# 1-Schematic_Illuno_Atmega328pu_V1.net
KiCad netlist of a schematic drawn in EasyEDA
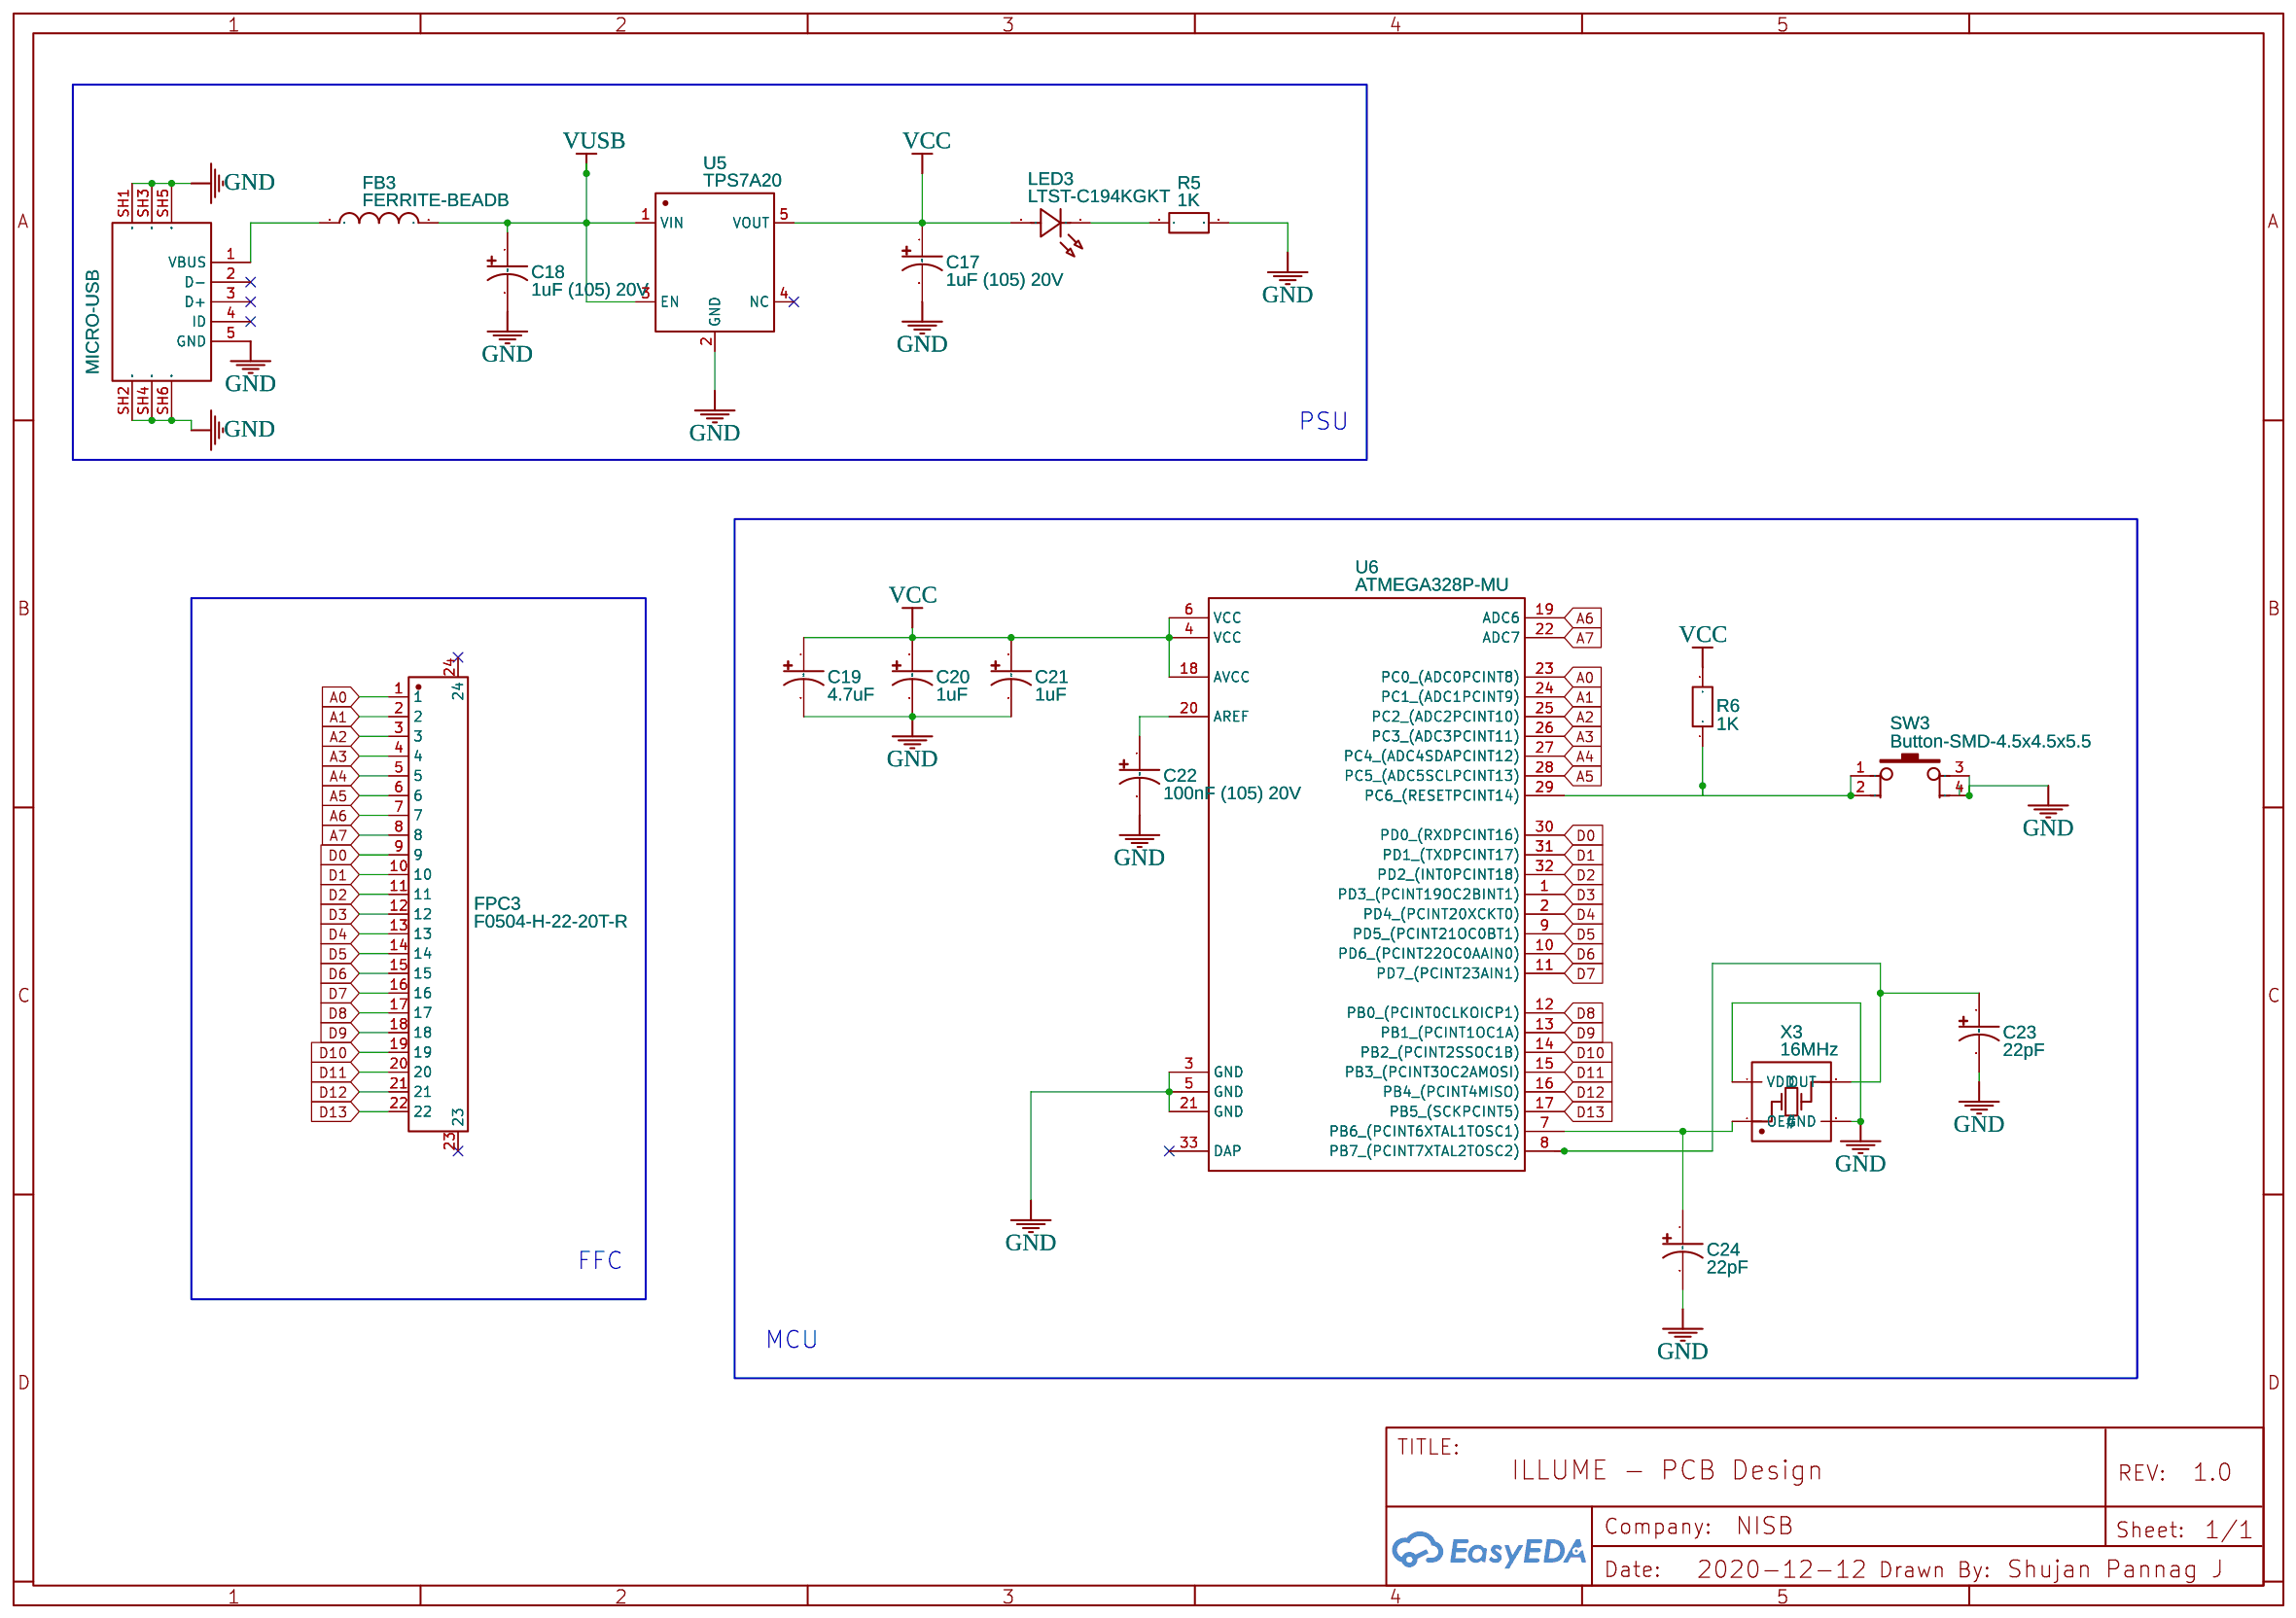
[diagram p0: schematic sheet]

(export (version "E")
  (design (tool "Eeschema 10.0.6"))
  (components
    (comp (ref "C17")
      (value "1uF (105) 20V")
      (fields (field (name "BOM_Supplier Part") "C28170"))
      (libsource (lib "") (part "1uF (105) 20V"))
    )
    (comp (ref "C18")
      (value "1uF (105) 20V")
      (fields (field (name "BOM_Supplier Part") "C28170"))
      (libsource (lib "") (part "1uF (105) 20V_2"))
    )
    (comp (ref "C19")
      (value "4.7uF")
      (fields (field (name "BOM_Supplier Part") "C28170"))
      (libsource (lib "") (part "1uF (105) 20V"))
    )
    (comp (ref "C20")
      (value "1uF")
      (fields (field (name "BOM_Supplier Part") "C28170"))
      (libsource (lib "") (part "1uF (105) 20V"))
    )
    (comp (ref "C21")
      (value "1uF")
      (fields (field (name "BOM_Supplier Part") "C28170"))
      (libsource (lib "") (part "1uF (105) 20V"))
    )
    (comp (ref "C22")
      (value "100nF (105) 20V")
      (fields (field (name "BOM_Supplier Part") "C28170"))
      (libsource (lib "") (part "1uF (105) 20V"))
    )
    (comp (ref "C23")
      (value "22pF")
      (fields (field (name "BOM_Supplier Part") "C28170"))
      (libsource (lib "") (part "1uF (105) 20V"))
    )
    (comp (ref "C24")
      (value "22pF")
      (fields (field (name "BOM_Supplier Part") "C28170"))
      (libsource (lib "") (part "1uF (105) 20V_1"))
    )
    (comp (ref "CN3")
      (value "MICRO-USB")
      (fields
        (field (name "BOM_Manufacturer Part") "MICRO 5PFemaleBtype")
        (field (name "BOM_Supplier Part") "C46390")
      )
      (libsource (lib "") (part "MICRO-USB-BF-5P"))
    )
    (comp (ref "FB3") (value "FERRITE-BEADB") (libsource (lib "") (part "FERRITE-BEADB")))
    (comp (ref "FPC3")
      (value "F0504-H-22-20T-R")
      (fields (field (name "BOM_Supplier Part") "C557729"))
      (libsource (lib "") (part "F0504-H-22-20T-R"))
    )
    (comp (ref "LED3")
      (value "LTST-C194KGKT")
      (fields (field (name "BOM_Supplier Part") "C913102"))
      (libsource (lib "") (part "LTST-C194KGKT"))
    )
    (comp (ref "R5")
      (value "1K")
      (fields
        (field (name "BOM_Manufacturer Part") "CR-05JA7---47K")
        (field (name "BOM_Supplier Part") "C881909")
      )
      (libsource (lib "") (part "CR-05JA7---47K"))
    )
    (comp (ref "R6")
      (value "1K")
      (fields
        (field (name "BOM_Manufacturer Part") "CR-05JA7---47K")
        (field (name "BOM_Supplier Part") "C881909")
      )
      (libsource (lib "") (part "CR-05JA7---47K_1"))
    )
    (comp (ref "SW3")
      (value "Button-SMD-4.5x4.5x5.5")
      (fields
        (field (name "BOM_Manufacturer Part") "4.5*4.5*5.5 Plastic head,260G, 0.25mm,SMD")
        (field (name "BOM_Supplier Part") "C71849")
      )
      (libsource (lib "") (part "Button-SMD-4.5x4.5x5.5"))
    )
    (comp (ref "U5") (value "TPS7A20") (libsource (lib "") (part "TPS7A20")))
    (comp (ref "U6")
      (value "ATMEGA328P-MU")
      (fields (field (name "BOM_Supplier Part") "C38896"))
      (libsource (lib "") (part "ATMEGA328P-MU"))
    )
    (comp (ref "X3")
      (value "16MHz")
      (fields (field (name "BOM_Supplier Part") "C160453"))
      (libsource (lib "") (part "HSO321S 27MHZ 3.3V"))
    )
  )
  (nets
    (net (code "1") (name "A0") (class "Default")
      (node (ref "FPC3") (pin "1") (pinfunction "1_1") (pintype "unspecified"))
      (node (ref "U6") (pin "23") (pinfunction "PC0_(ADC0PCINT8)_23") (pintype "bidirectional"))
    )
    (net (code "2") (name "A1") (class "Default")
      (node (ref "FPC3") (pin "2") (pinfunction "2_2") (pintype "unspecified"))
      (node (ref "U6") (pin "24") (pinfunction "PC1_(ADC1PCINT9)_24") (pintype "bidirectional"))
    )
    (net (code "3") (name "A2") (class "Default")
      (node (ref "FPC3") (pin "3") (pinfunction "3_3") (pintype "unspecified"))
      (node (ref "U6") (pin "25") (pinfunction "PC2_(ADC2PCINT10)_25") (pintype "bidirectional"))
    )
    (net (code "4") (name "A3") (class "Default")
      (node (ref "FPC3") (pin "4") (pinfunction "4_4") (pintype "unspecified"))
      (node (ref "U6") (pin "26") (pinfunction "PC3_(ADC3PCINT11)_26") (pintype "bidirectional"))
    )
    (net (code "5") (name "A4") (class "Default")
      (node (ref "FPC3") (pin "5") (pinfunction "5_5") (pintype "unspecified"))
      (node (ref "U6") (pin "27") (pinfunction "PC4_(ADC4SDAPCINT12)_27") (pintype "bidirectional"))
    )
    (net (code "6") (name "A5") (class "Default")
      (node (ref "FPC3") (pin "6") (pinfunction "6_6") (pintype "unspecified"))
      (node (ref "U6") (pin "28") (pinfunction "PC5_(ADC5SCLPCINT13)_28") (pintype "bidirectional"))
    )
    (net (code "7") (name "A6") (class "Default")
      (node (ref "FPC3") (pin "7") (pinfunction "7_7") (pintype "unspecified"))
      (node (ref "U6") (pin "19") (pinfunction "ADC6_19") (pintype "unspecified"))
    )
    (net (code "8") (name "A7") (class "Default")
      (node (ref "FPC3") (pin "8") (pinfunction "8_8") (pintype "unspecified"))
      (node (ref "U6") (pin "22") (pinfunction "ADC7_22") (pintype "unspecified"))
    )
    (net (code "9") (name "D0") (class "Default")
      (node (ref "FPC3") (pin "9") (pinfunction "9_9") (pintype "unspecified"))
      (node (ref "U6") (pin "30") (pinfunction "PD0_(RXDPCINT16)_30") (pintype "bidirectional"))
    )
    (net (code "10") (name "D1") (class "Default")
      (node (ref "FPC3") (pin "10") (pinfunction "10_10") (pintype "unspecified"))
      (node (ref "U6") (pin "31") (pinfunction "PD1_(TXDPCINT17)_31") (pintype "bidirectional"))
    )
    (net (code "11") (name "D2") (class "Default")
      (node (ref "FPC3") (pin "11") (pinfunction "11_11") (pintype "unspecified"))
      (node (ref "U6") (pin "32") (pinfunction "PD2_(INT0PCINT18)_32") (pintype "bidirectional"))
    )
    (net (code "12") (name "D3") (class "Default")
      (node (ref "FPC3") (pin "12") (pinfunction "12_12") (pintype "unspecified"))
      (node (ref "U6") (pin "1") (pinfunction "PD3_(PCINT19OC2BINT1)_1") (pintype "bidirectional"))
    )
    (net (code "13") (name "D4") (class "Default")
      (node (ref "FPC3") (pin "13") (pinfunction "13_13") (pintype "unspecified"))
      (node (ref "U6") (pin "2") (pinfunction "PD4_(PCINT20XCKT0)_2") (pintype "bidirectional"))
    )
    (net (code "14") (name "D5") (class "Default")
      (node (ref "FPC3") (pin "14") (pinfunction "14_14") (pintype "unspecified"))
      (node (ref "U6") (pin "9") (pinfunction "PD5_(PCINT21OC0BT1)_9") (pintype "bidirectional"))
    )
    (net (code "15") (name "D6") (class "Default")
      (node (ref "FPC3") (pin "15") (pinfunction "15_15") (pintype "unspecified"))
      (node (ref "U6") (pin "10") (pinfunction "PD6_(PCINT22OC0AAIN0)_10") (pintype "bidirectional"))
    )
    (net (code "16") (name "D7") (class "Default")
      (node (ref "FPC3") (pin "16") (pinfunction "16_16") (pintype "unspecified"))
      (node (ref "U6") (pin "11") (pinfunction "PD7_(PCINT23AIN1)_11") (pintype "bidirectional"))
    )
    (net (code "17") (name "D8") (class "Default")
      (node (ref "FPC3") (pin "17") (pinfunction "17_17") (pintype "unspecified"))
      (node (ref "U6") (pin "12") (pinfunction "PB0_(PCINT0CLKOICP1)_12") (pintype "bidirectional"))
    )
    (net (code "18") (name "D9") (class "Default")
      (node (ref "FPC3") (pin "18") (pinfunction "18_18") (pintype "unspecified"))
      (node (ref "U6") (pin "13") (pinfunction "PB1_(PCINT1OC1A)_13") (pintype "bidirectional"))
    )
    (net (code "19") (name "D10") (class "Default")
      (node (ref "FPC3") (pin "19") (pinfunction "19_19") (pintype "unspecified"))
      (node (ref "U6") (pin "14") (pinfunction "PB2_(PCINT2SSOC1B)_14") (pintype "bidirectional"))
    )
    (net (code "20") (name "D11") (class "Default")
      (node (ref "FPC3") (pin "20") (pinfunction "20_20") (pintype "unspecified"))
      (node (ref "U6") (pin "15") (pinfunction "PB3_(PCINT3OC2AMOSI)_15") (pintype "bidirectional"))
    )
    (net (code "21") (name "D12") (class "Default")
      (node (ref "FPC3") (pin "21") (pinfunction "21_21") (pintype "unspecified"))
      (node (ref "U6") (pin "16") (pinfunction "PB4_(PCINT4MISO)_16") (pintype "bidirectional"))
    )
    (net (code "22") (name "D13") (class "Default")
      (node (ref "FPC3") (pin "22") (pinfunction "22_22") (pintype "unspecified"))
      (node (ref "U6") (pin "17") (pinfunction "PB5_(SCKPCINT5)_17") (pintype "bidirectional"))
    )
    (net (code "23") (name "GND") (class "Default")
      (node (ref "C17") (pin "2") (pinfunction "2_2") (pintype "unspecified"))
      (node (ref "C18") (pin "2") (pinfunction "2_2") (pintype "unspecified"))
      (node (ref "C19") (pin "2") (pinfunction "2_2") (pintype "unspecified"))
      (node (ref "C20") (pin "2") (pinfunction "2_2") (pintype "unspecified"))
      (node (ref "C21") (pin "2") (pinfunction "2_2") (pintype "unspecified"))
      (node (ref "C22") (pin "2") (pinfunction "2_2") (pintype "unspecified"))
      (node (ref "C23") (pin "2") (pinfunction "2_2") (pintype "unspecified"))
      (node (ref "C24") (pin "2") (pinfunction "2_2") (pintype "unspecified"))
      (node (ref "CN3") (pin "5") (pinfunction "GND_5") (pintype "input"))
      (node (ref "CN3") (pin "SH1") (pinfunction "SH1_SH1") (pintype "input"))
      (node (ref "CN3") (pin "SH2") (pinfunction "SH2_SH2") (pintype "input"))
      (node (ref "CN3") (pin "SH3") (pinfunction "SH3_SH3") (pintype "input"))
      (node (ref "CN3") (pin "SH4") (pinfunction "SH4_SH4") (pintype "input"))
      (node (ref "CN3") (pin "SH5") (pinfunction "SH5_SH5") (pintype "input"))
      (node (ref "CN3") (pin "SH6") (pinfunction "SH6_SH6") (pintype "input"))
      (node (ref "R5") (pin "2") (pinfunction "2_2") (pintype "unspecified"))
      (node (ref "SW3") (pin "3") (pinfunction "3_3") (pintype "input"))
      (node (ref "SW3") (pin "4") (pinfunction "4_4") (pintype "input"))
      (node (ref "U5") (pin "2") (pinfunction "GND_2") (pintype "unspecified"))
      (node (ref "U6") (pin "21") (pinfunction "GND_21") (pintype "passive"))
      (node (ref "U6") (pin "3") (pinfunction "GND_3") (pintype "passive"))
      (node (ref "U6") (pin "5") (pinfunction "GND_5") (pintype "passive"))
      (node (ref "X3") (pin "2") (pinfunction "GND_2") (pintype "input"))
      (node (ref "X3") (pin "4") (pinfunction "VDD_4") (pintype "input"))
    )
    (net (code "24") (name "Net-(CN3-VBUS)") (class "Default")
      (node (ref "CN3") (pin "1") (pinfunction "VBUS_1") (pintype "input"))
      (node (ref "FB3") (pin "1") (pinfunction "1_1") (pintype "unspecified"))
    )
    (net (code "25") (name "Net-(LED3-K)") (class "Default")
      (node (ref "LED3") (pin "1") (pinfunction "K_1") (pintype "unspecified"))
      (node (ref "R5") (pin "1") (pinfunction "1_1") (pintype "unspecified"))
    )
    (net (code "26") (name "Net-(U6-AREF)") (class "Default")
      (node (ref "C22") (pin "1") (pinfunction "1_1") (pintype "unspecified"))
      (node (ref "U6") (pin "20") (pinfunction "AREF_20") (pintype "unspecified"))
    )
    (net (code "27") (name "Net-(U6-PB6_(PCINT6XTAL1TOSC1))") (class "Default")
      (node (ref "C24") (pin "1") (pinfunction "1_1") (pintype "unspecified"))
      (node (ref "U6") (pin "7") (pinfunction "PB6_(PCINT6XTAL1TOSC1)_7") (pintype "bidirectional"))
      (node (ref "X3") (pin "1") (pinfunction "OE#_1") (pintype "input"))
    )
    (net (code "28") (name "Net-(U6-PB7_(PCINT7XTAL2TOSC2))") (class "Default")
      (node (ref "C23") (pin "1") (pinfunction "1_1") (pintype "unspecified"))
      (node (ref "U6") (pin "8") (pinfunction "PB7_(PCINT7XTAL2TOSC2)_8") (pintype "bidirectional"))
      (node (ref "X3") (pin "3") (pinfunction "OUT_3") (pintype "input"))
    )
    (net (code "29") (name "Net-(U6-PC6_(RESETPCINT14))") (class "Default")
      (node (ref "R6") (pin "1") (pinfunction "1_1") (pintype "unspecified"))
      (node (ref "SW3") (pin "1") (pinfunction "1_1") (pintype "input"))
      (node (ref "SW3") (pin "2") (pinfunction "2_2") (pintype "input"))
      (node (ref "U6") (pin "29") (pinfunction "PC6_(RESETPCINT14)_29") (pintype "bidirectional"))
    )
    (net (code "30") (name "VCC") (class "Default")
      (node (ref "C17") (pin "1") (pinfunction "1_1") (pintype "unspecified"))
      (node (ref "C19") (pin "1") (pinfunction "1_1") (pintype "unspecified"))
      (node (ref "C20") (pin "1") (pinfunction "1_1") (pintype "unspecified"))
      (node (ref "C21") (pin "1") (pinfunction "1_1") (pintype "unspecified"))
      (node (ref "LED3") (pin "2") (pinfunction "A_2") (pintype "unspecified"))
      (node (ref "R6") (pin "2") (pinfunction "2_2") (pintype "unspecified"))
      (node (ref "U5") (pin "5") (pinfunction "VOUT_5") (pintype "unspecified"))
      (node (ref "U6") (pin "18") (pinfunction "AVCC_18") (pintype "passive"))
      (node (ref "U6") (pin "4") (pinfunction "VCC_4") (pintype "passive"))
      (node (ref "U6") (pin "6") (pinfunction "VCC_6") (pintype "passive"))
    )
    (net (code "31") (name "VUSB") (class "Default")
      (node (ref "C18") (pin "1") (pinfunction "1_1") (pintype "unspecified"))
      (node (ref "FB3") (pin "2") (pinfunction "2_2") (pintype "unspecified"))
      (node (ref "U5") (pin "1") (pinfunction "VIN_1") (pintype "unspecified"))
      (node (ref "U5") (pin "3") (pinfunction "EN_3") (pintype "unspecified"))
    )
    (net (code "32") (name "unconnected-(CN3-D+-Pad3)") (class "Default")
      (node (ref "CN3") (pin "3") (pinfunction "D+_3") (pintype "input+no_connect"))
    )
    (net (code "33") (name "unconnected-(CN3-D--Pad2)") (class "Default")
      (node (ref "CN3") (pin "2") (pinfunction "D-_2") (pintype "input+no_connect"))
    )
    (net (code "34") (name "unconnected-(CN3-ID-Pad4)") (class "Default")
      (node (ref "CN3") (pin "4") (pinfunction "ID_4") (pintype "input+no_connect"))
    )
    (net (code "35") (name "unconnected-(FPC3-Pad23)") (class "Default")
      (node (ref "FPC3") (pin "23") (pinfunction "23_23") (pintype "unspecified+no_connect"))
    )
    (net (code "36") (name "unconnected-(FPC3-Pad24)") (class "Default")
      (node (ref "FPC3") (pin "24") (pinfunction "24_24") (pintype "unspecified+no_connect"))
    )
    (net (code "37") (name "unconnected-(U5-NC-Pad4)") (class "Default")
      (node (ref "U5") (pin "4") (pinfunction "NC_4") (pintype "unspecified+no_connect"))
    )
    (net (code "38") (name "unconnected-(U6-DAP-Pad33)") (class "Default")
      (node (ref "U6") (pin "33") (pinfunction "DAP_33") (pintype "passive+no_connect"))
    )
  )
)
